# peppermill.net
KiCad netlist of a schematic drawn in EAGLE
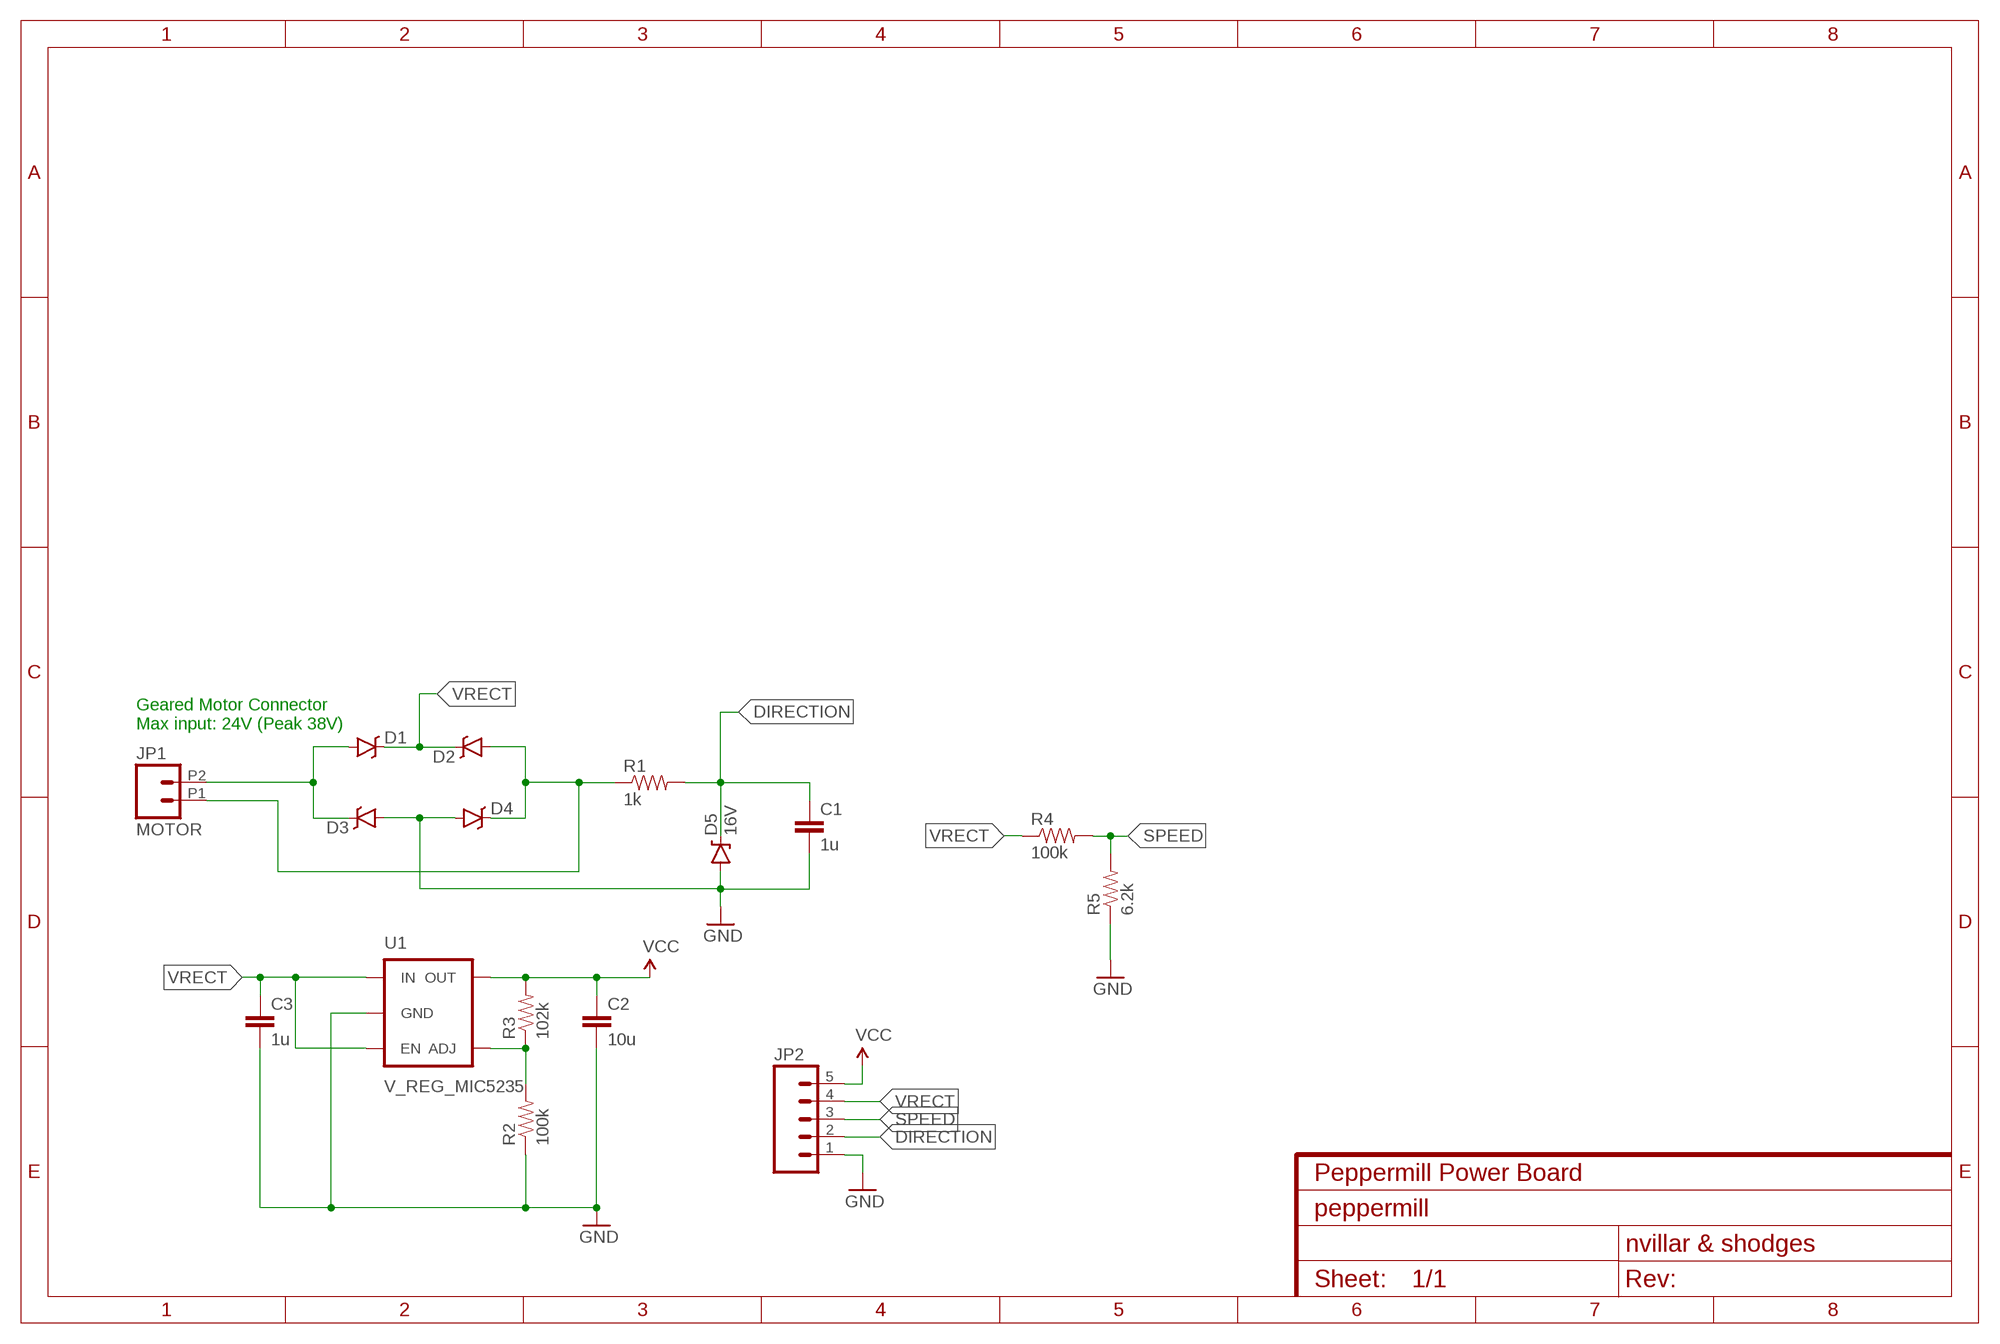
[diagram p0: schematic, sheet 1]

(export (version "E")
  (design (tool "Eeschema 10.0.6"))
  (components
    (comp (ref "C1")
      (value "1u")
      (footprint "eagle-import:0805")
      (libsource (lib "eagle-import") (part "CAP0805"))
    )
    (comp (ref "C2")
      (value "10u")
      (footprint "eagle-import:0805")
      (libsource (lib "eagle-import") (part "CAP0805"))
    )
    (comp (ref "C3")
      (value "1u")
      (footprint "eagle-import:0805")
      (libsource (lib "eagle-import") (part "CAP0805"))
    )
    (comp (ref "D1")
      (value "BAT20JFILM")
      (footprint "eagle-import:SOD-323")
      (libsource (lib "eagle-import") (part "BAT20JFILM"))
    )
    (comp (ref "D2")
      (value "BAT20JFILM")
      (footprint "eagle-import:SOD-323")
      (libsource (lib "eagle-import") (part "BAT20JFILM"))
    )
    (comp (ref "D3")
      (value "BAT20JFILM")
      (footprint "eagle-import:SOD-323")
      (libsource (lib "eagle-import") (part "BAT20JFILM"))
    )
    (comp (ref "D4")
      (value "BAT20JFILM")
      (footprint "eagle-import:SOD-323")
      (libsource (lib "eagle-import") (part "BAT20JFILM"))
    )
    (comp (ref "D5")
      (value "16V")
      (footprint "eagle-import:SOD-123")
      (libsource (lib "eagle-import") (part "DIODE-ZENER16V"))
    )
    (comp (ref "JP1")
      (value "MOTOR")
      (footprint "eagle-import:1X02_2.54_SCREWTERM")
      (libsource (lib "eagle-import") (part "M022.54MM_SCREWTERM"))
    )
    (comp (ref "JP2")
      (value "M05LOCK")
      (footprint "eagle-import:1X05_LOCK")
      (libsource (lib "eagle-import") (part "M05LOCK"))
    )
    (comp (ref "R1")
      (value "1k")
      (footprint "eagle-import:0805")
      (libsource (lib "eagle-import") (part "RESISTOR0805-RES"))
    )
    (comp (ref "R2")
      (value "100k")
      (footprint "eagle-import:0805")
      (libsource (lib "eagle-import") (part "RESISTOR0805-RES"))
    )
    (comp (ref "R3")
      (value "102k")
      (footprint "eagle-import:0805")
      (libsource (lib "eagle-import") (part "RESISTOR0805-RES"))
    )
    (comp (ref "R4")
      (value "100k")
      (footprint "eagle-import:0805")
      (libsource (lib "eagle-import") (part "RESISTOR0805-RES"))
    )
    (comp (ref "R5")
      (value "6.2k")
      (footprint "eagle-import:0805")
      (libsource (lib "eagle-import") (part "RESISTOR0805-RES"))
    )
    (comp (ref "U1")
      (value "V_REG_MIC5235")
      (footprint "eagle-import:SOT23-5")
      (libsource (lib "eagle-import") (part "V_REG_MIC5235"))
    )
  )
  (nets
    (net (code "1") (name "DIRECTION") (class "Default")
      (node (ref "C1") (pin "1") (pinfunction "1_1") (pintype "passive"))
      (node (ref "D5") (pin "C") (pinfunction "C_C") (pintype "passive"))
      (node (ref "JP2") (pin "2") (pinfunction "2_2") (pintype "passive"))
      (node (ref "R1") (pin "2") (pinfunction "2_2") (pintype "passive"))
    )
    (net (code "2") (name "GND") (class "Default")
      (node (ref "C1") (pin "2") (pinfunction "2_2") (pintype "passive"))
      (node (ref "C2") (pin "2") (pinfunction "2_2") (pintype "passive"))
      (node (ref "C3") (pin "2") (pinfunction "2_2") (pintype "passive"))
      (node (ref "D3") (pin "A") (pinfunction "A_A") (pintype "passive"))
      (node (ref "D4") (pin "A") (pinfunction "A_A") (pintype "passive"))
      (node (ref "D5") (pin "A") (pinfunction "A_A") (pintype "passive"))
      (node (ref "JP2") (pin "1") (pinfunction "1_1") (pintype "passive"))
      (node (ref "R2") (pin "1") (pinfunction "1_1") (pintype "passive"))
      (node (ref "R5") (pin "1") (pinfunction "1_1") (pintype "passive"))
      (node (ref "U1") (pin "2") (pinfunction "GND_2") (pintype "input"))
    )
    (net (code "3") (name "Net-(JP1-1)") (class "Default")
      (node (ref "D2") (pin "A") (pinfunction "A_A") (pintype "passive"))
      (node (ref "D4") (pin "C") (pinfunction "C_C") (pintype "passive"))
      (node (ref "JP1") (pin "P1") (pinfunction "1_P1") (pintype "passive"))
      (node (ref "R1") (pin "1") (pinfunction "1_1") (pintype "passive"))
    )
    (net (code "4") (name "Net-(JP1-2)") (class "Default")
      (node (ref "D1") (pin "A") (pinfunction "A_A") (pintype "passive"))
      (node (ref "D3") (pin "C") (pinfunction "C_C") (pintype "passive"))
      (node (ref "JP1") (pin "P2") (pinfunction "2_P2") (pintype "passive"))
    )
    (net (code "5") (name "Net-(U1-ADJ)") (class "Default")
      (node (ref "R2") (pin "2") (pinfunction "2_2") (pintype "passive"))
      (node (ref "R3") (pin "1") (pinfunction "1_1") (pintype "passive"))
      (node (ref "U1") (pin "4") (pinfunction "ADJ_4") (pintype "input"))
    )
    (net (code "6") (name "SPEED") (class "Default")
      (node (ref "JP2") (pin "3") (pinfunction "3_3") (pintype "passive"))
      (node (ref "R4") (pin "2") (pinfunction "2_2") (pintype "passive"))
      (node (ref "R5") (pin "2") (pinfunction "2_2") (pintype "passive"))
    )
    (net (code "7") (name "VCC") (class "Default")
      (node (ref "C2") (pin "1") (pinfunction "1_1") (pintype "passive"))
      (node (ref "JP2") (pin "5") (pinfunction "5_5") (pintype "passive"))
      (node (ref "R3") (pin "2") (pinfunction "2_2") (pintype "passive"))
      (node (ref "U1") (pin "5") (pinfunction "OUT_5") (pintype "passive"))
    )
    (net (code "8") (name "VRECT") (class "Default")
      (node (ref "C3") (pin "1") (pinfunction "1_1") (pintype "passive"))
      (node (ref "D1") (pin "C") (pinfunction "C_C") (pintype "passive"))
      (node (ref "D2") (pin "C") (pinfunction "C_C") (pintype "passive"))
      (node (ref "JP2") (pin "4") (pinfunction "4_4") (pintype "passive"))
      (node (ref "R4") (pin "1") (pinfunction "1_1") (pintype "passive"))
      (node (ref "U1") (pin "1") (pinfunction "IN_1") (pintype "input"))
      (node (ref "U1") (pin "3") (pinfunction "EN_3") (pintype "input"))
    )
  )
)
